# LCD_Display.net
KiCad netlist of a schematic drawn in Altium Designer
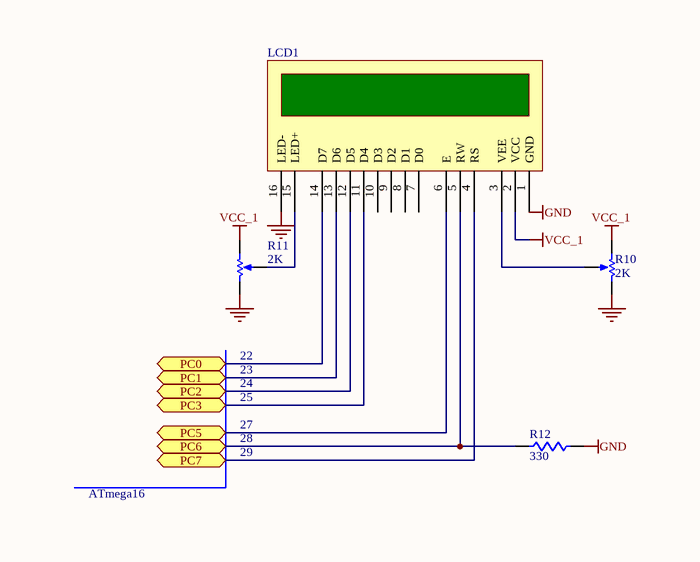
[diagram p0: LCD Display.SchDoc]

(export (version "E")
  (design (tool "Eeschema 10.0.6"))
  (components
    (comp (ref "LCD1")
      (value "LCD_16*2")
      (footprint "LCD_2x16")
      (libsource (lib "my Libraries") (part "LCD_16*2"))
    )
    (comp (ref "R10")
      (value "2K")
      (footprint "VR8-5/5.6MM")
      (description "Potentiometer")
      (fields
        (field (name "MANUFACTURER") "Generic Components")
        (field (name "Comment") "RPot1")
        (field (name "PUBLISHER") "Altium Limited")
      )
      (libsource (lib "my Libraries") (part "RPot1"))
    )
    (comp (ref "R11")
      (value "2K")
      (footprint "VR8-5/5.6MM")
      (description "Potentiometer")
      (fields
        (field (name "MANUFACTURER") "Generic Components")
        (field (name "Comment") "RPot1")
        (field (name "PUBLISHER") "Altium Limited")
      )
      (libsource (lib "my Libraries") (part "RPot1"))
    )
    (comp (ref "R12")
      (value "330")
      (footprint "AXIAL0.4")
      (description "Resistor")
      (fields (field (name "MANUFACTURER") "Generic Components") (field (name "PUBLISHER") "Altium Limited"))
      (libsource (lib "my Libraries") (part "Resistor"))
    )
  )
  (nets
    (net (code "1") (name "/PC0") (class "Default")
      (node (ref "LCD1") (pin "14") (pinfunction "D7_14") (pintype "passive"))
    )
    (net (code "2") (name "/PC1") (class "Default")
      (node (ref "LCD1") (pin "13") (pinfunction "D6_13") (pintype "passive"))
    )
    (net (code "3") (name "/PC2") (class "Default")
      (node (ref "LCD1") (pin "12") (pinfunction "D5_12") (pintype "passive"))
    )
    (net (code "4") (name "/PC3") (class "Default")
      (node (ref "LCD1") (pin "11") (pinfunction "D4_11") (pintype "passive"))
    )
    (net (code "5") (name "/PC5") (class "Default")
      (node (ref "LCD1") (pin "6") (pinfunction "E_6") (pintype "passive"))
    )
    (net (code "6") (name "/PC6") (class "Default")
      (node (ref "LCD1") (pin "5") (pinfunction "RW_5") (pintype "passive"))
      (node (ref "R12") (pin "2") (pinfunction "2_2") (pintype "passive"))
    )
    (net (code "7") (name "/PC7") (class "Default")
      (node (ref "LCD1") (pin "4") (pinfunction "RS_4") (pintype "passive"))
    )
    (net (code "8") (name "GND") (class "Default")
      (node (ref "LCD1") (pin "1") (pinfunction "GND_1") (pintype "passive"))
      (node (ref "LCD1") (pin "16") (pinfunction "LED-_16") (pintype "passive"))
      (node (ref "R10") (pin "1") (pinfunction "TOP_1") (pintype "passive"))
      (node (ref "R11") (pin "2") (pinfunction "BOT_2") (pintype "passive"))
      (node (ref "R12") (pin "1") (pinfunction "1_1") (pintype "passive"))
    )
    (net (code "9") (name "Net-(LCD1-LED+)") (class "Default")
      (node (ref "LCD1") (pin "15") (pinfunction "LED+_15") (pintype "passive"))
      (node (ref "R11") (pin "3") (pinfunction "TAP_3") (pintype "passive"))
    )
    (net (code "10") (name "Net-(LCD1-VEE)") (class "Default")
      (node (ref "LCD1") (pin "3") (pinfunction "VEE_3") (pintype "passive"))
      (node (ref "R10") (pin "3") (pinfunction "TAP_3") (pintype "passive"))
    )
    (net (code "11") (name "VCC_1") (class "Default")
      (node (ref "LCD1") (pin "2") (pinfunction "VCC_2") (pintype "passive"))
      (node (ref "R10") (pin "2") (pinfunction "BOT_2") (pintype "passive"))
      (node (ref "R11") (pin "1") (pinfunction "TOP_1") (pintype "passive"))
    )
    (net (code "12") (name "unconnected-(LCD1-D0-Pad7)") (class "Default")
      (node (ref "LCD1") (pin "7") (pinfunction "D0_7") (pintype "passive"))
    )
    (net (code "13") (name "unconnected-(LCD1-D1-Pad8)") (class "Default")
      (node (ref "LCD1") (pin "8") (pinfunction "D1_8") (pintype "passive"))
    )
    (net (code "14") (name "unconnected-(LCD1-D2-Pad9)") (class "Default")
      (node (ref "LCD1") (pin "9") (pinfunction "D2_9") (pintype "passive"))
    )
    (net (code "15") (name "unconnected-(LCD1-D3-Pad10)") (class "Default")
      (node (ref "LCD1") (pin "10") (pinfunction "D3_10") (pintype "passive"))
    )
  )
)
